# motor_connector_board.net
KiCad netlist of a schematic drawn in EAGLE
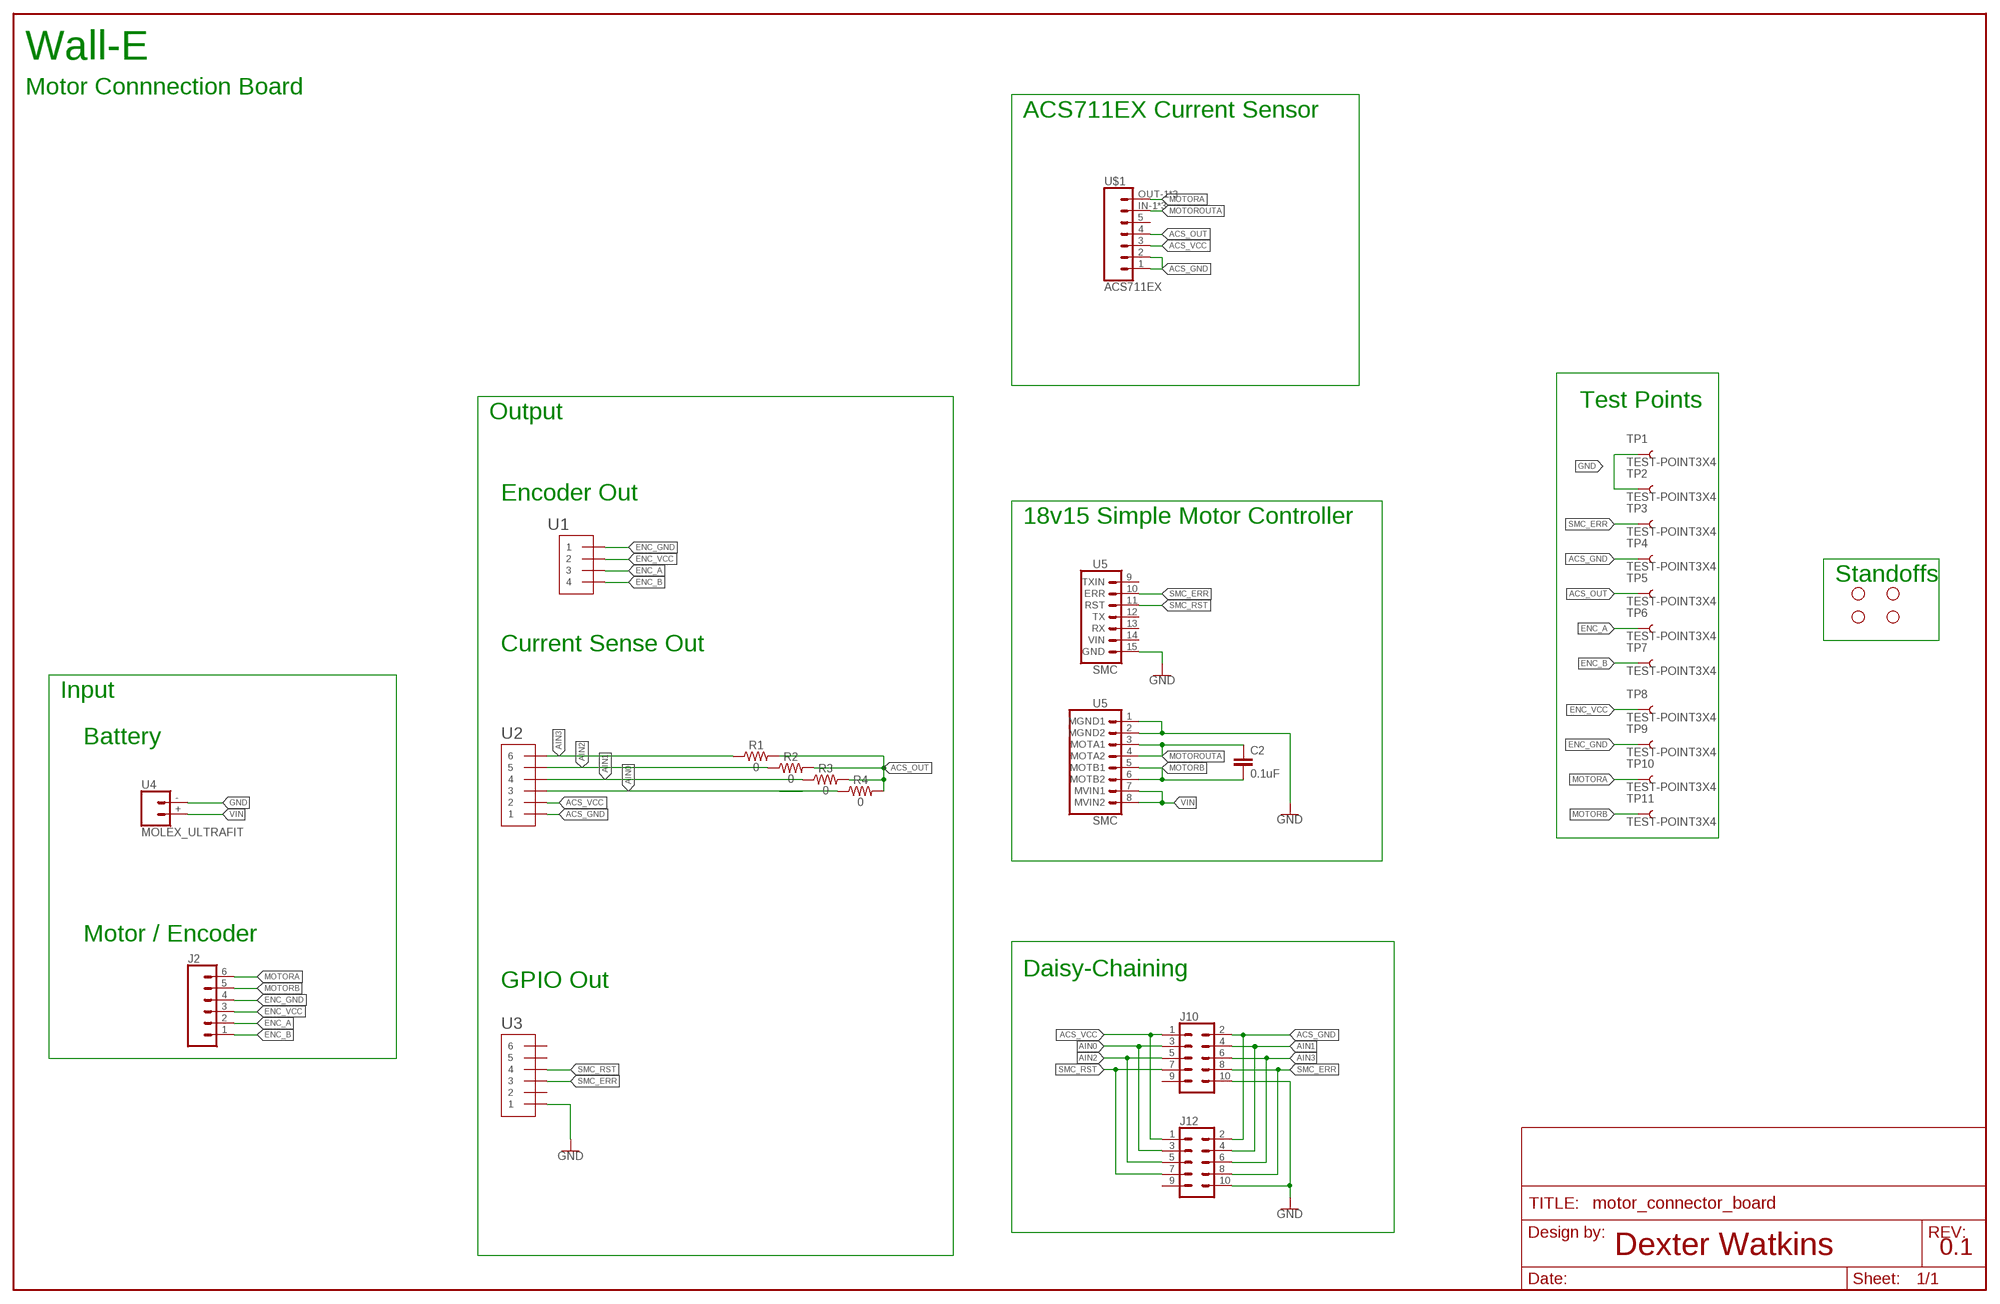
[diagram p0: schematic, sheet 1]

(export (version "E")
  (design (tool "Eeschema 10.0.6"))
  (components
    (comp (ref "C2")
      (value "0.1uF")
      (footprint "eagle-import:0603")
      (libsource (lib "eagle-import") (part "1.0NF/1000PF-0603-50V-10%"))
    )
    (comp (ref "FRAME1")
      (value "FRAME-LEDGER")
      (footprint "eagle-import:CREATIVE_COMMONS")
      (libsource (lib "eagle-import") (part "FRAME-LEDGER"))
    )
    (comp (ref "H1")
      (value "STAND-OFF")
      (footprint "eagle-import:STAND-OFF")
      (libsource (lib "eagle-import") (part "STAND-OFF"))
    )
    (comp (ref "H2")
      (value "STAND-OFF")
      (footprint "eagle-import:STAND-OFF")
      (libsource (lib "eagle-import") (part "STAND-OFF"))
    )
    (comp (ref "H3")
      (value "STAND-OFF")
      (footprint "eagle-import:STAND-OFF")
      (libsource (lib "eagle-import") (part "STAND-OFF"))
    )
    (comp (ref "H4")
      (value "STAND-OFF")
      (footprint "eagle-import:STAND-OFF")
      (libsource (lib "eagle-import") (part "STAND-OFF"))
    )
    (comp (ref "J2")
      (value "CONN_06LONGPADS")
      (footprint "eagle-import:1X06_LONGPADS")
      (libsource (lib "eagle-import") (part "CONN_06LONGPADS"))
    )
    (comp (ref "J10")
      (value "CONN_05X2SHD_LOCK")
      (footprint "eagle-import:2X5-SHROUDED_LOCK")
      (libsource (lib "eagle-import") (part "CONN_05X2SHD_LOCK"))
    )
    (comp (ref "J12")
      (value "CONN_05X2SHD_LOCK")
      (footprint "eagle-import:2X5-SHROUDED_LOCK")
      (libsource (lib "eagle-import") (part "CONN_05X2SHD_LOCK"))
    )
    (comp (ref "R1")
      (value "0")
      (footprint "eagle-import:0603")
      (libsource (lib "eagle-import") (part "0OHM-0603-1/10W-5%"))
    )
    (comp (ref "R2")
      (value "0")
      (footprint "eagle-import:0603")
      (libsource (lib "eagle-import") (part "0OHM-0603-1/10W-5%"))
    )
    (comp (ref "R3")
      (value "0")
      (footprint "eagle-import:0603")
      (libsource (lib "eagle-import") (part "0OHM-0603-1/10W-5%"))
    )
    (comp (ref "R4")
      (value "0")
      (footprint "eagle-import:0603")
      (libsource (lib "eagle-import") (part "0OHM-0603-1/10W-5%"))
    )
    (comp (ref "TP1")
      (value "TEST-POINT3X4")
      (footprint "eagle-import:PAD.03X.04")
      (libsource (lib "eagle-import") (part "TEST-POINT3X4"))
    )
    (comp (ref "TP2")
      (value "TEST-POINT3X4")
      (footprint "eagle-import:PAD.03X.04")
      (libsource (lib "eagle-import") (part "TEST-POINT3X4"))
    )
    (comp (ref "TP3")
      (value "TEST-POINT3X4")
      (footprint "eagle-import:PAD.03X.04")
      (libsource (lib "eagle-import") (part "TEST-POINT3X4"))
    )
    (comp (ref "TP4")
      (value "TEST-POINT3X4")
      (footprint "eagle-import:PAD.03X.04")
      (libsource (lib "eagle-import") (part "TEST-POINT3X4"))
    )
    (comp (ref "TP5")
      (value "TEST-POINT3X4")
      (footprint "eagle-import:PAD.03X.04")
      (libsource (lib "eagle-import") (part "TEST-POINT3X4"))
    )
    (comp (ref "TP6")
      (value "TEST-POINT3X4")
      (footprint "eagle-import:PAD.03X.04")
      (libsource (lib "eagle-import") (part "TEST-POINT3X4"))
    )
    (comp (ref "TP7")
      (value "TEST-POINT3X4")
      (footprint "eagle-import:PAD.03X.04")
      (libsource (lib "eagle-import") (part "TEST-POINT3X4"))
    )
    (comp (ref "TP8")
      (value "TEST-POINT3X4")
      (footprint "eagle-import:PAD.03X.04")
      (libsource (lib "eagle-import") (part "TEST-POINT3X4"))
    )
    (comp (ref "TP9")
      (value "TEST-POINT3X4")
      (footprint "eagle-import:PAD.03X.04")
      (libsource (lib "eagle-import") (part "TEST-POINT3X4"))
    )
    (comp (ref "TP10")
      (value "TEST-POINT3X4")
      (footprint "eagle-import:PAD.03X.04")
      (libsource (lib "eagle-import") (part "TEST-POINT3X4"))
    )
    (comp (ref "TP11")
      (value "TEST-POINT3X4")
      (footprint "eagle-import:PAD.03X.04")
      (libsource (lib "eagle-import") (part "TEST-POINT3X4"))
    )
    (comp (ref "U$1")
      (value "ACS711EX")
      (footprint "eagle-import:ACS_CURRENT_SENSOR")
      (libsource (lib "eagle-import") (part "ACS711EX"))
    )
    (comp (ref "U1")
      (value "JST_SH_4")
      (footprint "eagle-import:JST_SH_4_SMD")
      (libsource (lib "eagle-import") (part "JST_SH_4"))
    )
    (comp (ref "U2")
      (value "JST_SH_6")
      (footprint "eagle-import:JST_SH_6")
      (libsource (lib "eagle-import") (part "JST_SH_6"))
    )
    (comp (ref "U3")
      (value "JST_SH_6")
      (footprint "eagle-import:JST_SH_6")
      (libsource (lib "eagle-import") (part "JST_SH_6"))
    )
    (comp (ref "U4")
      (value "MOLEX_ULTRAFIT")
      (footprint "eagle-import:MOLEX_ULTRAFIT-2CKT")
      (libsource (lib "eagle-import") (part "MOLEX_ULTRAFIT"))
    )
    (comp (ref "U5")
      (value "SMC")
      (footprint "eagle-import:SMC")
      (libsource (lib "eagle-import") (part "SMC"))
    )
  )
  (nets
    (net (code "1") (name "ACS_GND") (class "Default")
      (node (ref "J10") (pin "2") (pinfunction "2_2") (pintype "passive"))
      (node (ref "J12") (pin "2") (pinfunction "2_2") (pintype "passive"))
      (node (ref "TP4") (pin "P$1") (pinfunction "1_P$1") (pintype "bidirectional"))
      (node (ref "U$1") (pin "1") (pinfunction "1_1") (pintype "passive"))
      (node (ref "U$1") (pin "2") (pinfunction "2_2") (pintype "passive"))
      (node (ref "U2") (pin "1") (pinfunction "1_1") (pintype "bidirectional"))
    )
    (net (code "2") (name "ACS_OUT") (class "Default")
      (node (ref "R1") (pin "2") (pinfunction "2_2") (pintype "passive"))
      (node (ref "R2") (pin "2") (pinfunction "2_2") (pintype "passive"))
      (node (ref "R3") (pin "2") (pinfunction "2_2") (pintype "passive"))
      (node (ref "R4") (pin "2") (pinfunction "2_2") (pintype "passive"))
      (node (ref "TP5") (pin "P$1") (pinfunction "1_P$1") (pintype "bidirectional"))
      (node (ref "U$1") (pin "4") (pinfunction "4_4") (pintype "passive"))
    )
    (net (code "3") (name "ACS_VCC") (class "Default")
      (node (ref "J10") (pin "1") (pinfunction "1_1") (pintype "passive"))
      (node (ref "J12") (pin "1") (pinfunction "1_1") (pintype "passive"))
      (node (ref "U$1") (pin "3") (pinfunction "3_3") (pintype "passive"))
      (node (ref "U2") (pin "2") (pinfunction "2_2") (pintype "bidirectional"))
    )
    (net (code "4") (name "AIN0") (class "Default")
      (node (ref "J10") (pin "3") (pinfunction "3_3") (pintype "passive"))
      (node (ref "J12") (pin "3") (pinfunction "3_3") (pintype "passive"))
      (node (ref "R4") (pin "1") (pinfunction "1_1") (pintype "passive"))
      (node (ref "U2") (pin "3") (pinfunction "3_3") (pintype "bidirectional"))
    )
    (net (code "5") (name "AIN1") (class "Default")
      (node (ref "J10") (pin "4") (pinfunction "4_4") (pintype "passive"))
      (node (ref "J12") (pin "4") (pinfunction "4_4") (pintype "passive"))
      (node (ref "R3") (pin "1") (pinfunction "1_1") (pintype "passive"))
      (node (ref "U2") (pin "4") (pinfunction "4_4") (pintype "bidirectional"))
    )
    (net (code "6") (name "AIN2") (class "Default")
      (node (ref "J10") (pin "5") (pinfunction "5_5") (pintype "passive"))
      (node (ref "J12") (pin "5") (pinfunction "5_5") (pintype "passive"))
      (node (ref "R2") (pin "1") (pinfunction "1_1") (pintype "passive"))
      (node (ref "U2") (pin "5") (pinfunction "5_5") (pintype "bidirectional"))
    )
    (net (code "7") (name "AIN3") (class "Default")
      (node (ref "J10") (pin "6") (pinfunction "6_6") (pintype "passive"))
      (node (ref "J12") (pin "6") (pinfunction "6_6") (pintype "passive"))
      (node (ref "R1") (pin "1") (pinfunction "1_1") (pintype "passive"))
      (node (ref "U2") (pin "6") (pinfunction "6_6") (pintype "bidirectional"))
    )
    (net (code "8") (name "ENC_A") (class "Default")
      (node (ref "J2") (pin "2") (pinfunction "2_2") (pintype "passive"))
      (node (ref "TP6") (pin "P$1") (pinfunction "1_P$1") (pintype "bidirectional"))
      (node (ref "U1") (pin "3") (pinfunction "3_3") (pintype "bidirectional"))
    )
    (net (code "9") (name "ENC_B") (class "Default")
      (node (ref "J2") (pin "1") (pinfunction "1_1") (pintype "passive"))
      (node (ref "TP7") (pin "P$1") (pinfunction "1_P$1") (pintype "bidirectional"))
      (node (ref "U1") (pin "4") (pinfunction "4_4") (pintype "bidirectional"))
    )
    (net (code "10") (name "ENC_GND") (class "Default")
      (node (ref "J2") (pin "4") (pinfunction "4_4") (pintype "passive"))
      (node (ref "TP9") (pin "P$1") (pinfunction "1_P$1") (pintype "bidirectional"))
      (node (ref "U1") (pin "1") (pinfunction "1_1") (pintype "bidirectional"))
    )
    (net (code "11") (name "ENC_VCC") (class "Default")
      (node (ref "J2") (pin "3") (pinfunction "3_3") (pintype "passive"))
      (node (ref "TP8") (pin "P$1") (pinfunction "1_P$1") (pintype "bidirectional"))
      (node (ref "U1") (pin "2") (pinfunction "2_2") (pintype "bidirectional"))
    )
    (net (code "12") (name "GND") (class "Default")
      (node (ref "J10") (pin "10") (pinfunction "10_10") (pintype "passive"))
      (node (ref "J12") (pin "10") (pinfunction "10_10") (pintype "passive"))
      (node (ref "TP1") (pin "P$1") (pinfunction "1_P$1") (pintype "bidirectional"))
      (node (ref "TP2") (pin "P$1") (pinfunction "1_P$1") (pintype "bidirectional"))
      (node (ref "U3") (pin "1") (pinfunction "1_1") (pintype "bidirectional"))
      (node (ref "U4") (pin "-") (pinfunction "2_-") (pintype "passive"))
      (node (ref "U5") (pin "1") (pinfunction "MGND1_1") (pintype "passive"))
      (node (ref "U5") (pin "15") (pinfunction "GND_15") (pintype "passive"))
      (node (ref "U5") (pin "2") (pinfunction "MGND2_2") (pintype "passive"))
    )
    (net (code "13") (name "MOTORA") (class "Default")
      (node (ref "J2") (pin "6") (pinfunction "6_6") (pintype "passive"))
      (node (ref "TP10") (pin "P$1") (pinfunction "1_P$1") (pintype "bidirectional"))
      (node (ref "U$1") (pin "OUT-1") (pinfunction "7_OUT-1") (pintype "passive"))
      (node (ref "U$1") (pin "OUT-2") (pinfunction "7_OUT-2") (pintype "passive"))
      (node (ref "U$1") (pin "OUT-3") (pinfunction "7_OUT-3") (pintype "passive"))
    )
    (net (code "14") (name "MOTORB") (class "Default")
      (node (ref "C2") (pin "2") (pinfunction "2_2") (pintype "passive"))
      (node (ref "J2") (pin "5") (pinfunction "5_5") (pintype "passive"))
      (node (ref "TP11") (pin "P$1") (pinfunction "1_P$1") (pintype "bidirectional"))
      (node (ref "U5") (pin "5") (pinfunction "MOTB1_5") (pintype "passive"))
      (node (ref "U5") (pin "6") (pinfunction "MOTB2_6") (pintype "passive"))
    )
    (net (code "15") (name "MOTOROUTA") (class "Default")
      (node (ref "C2") (pin "1") (pinfunction "1_1") (pintype "passive"))
      (node (ref "U$1") (pin "IN-1") (pinfunction "6_IN-1") (pintype "passive"))
      (node (ref "U$1") (pin "IN-2") (pinfunction "6_IN-2") (pintype "passive"))
      (node (ref "U$1") (pin "IN-3") (pinfunction "6_IN-3") (pintype "passive"))
      (node (ref "U5") (pin "3") (pinfunction "MOTA1_3") (pintype "passive"))
      (node (ref "U5") (pin "4") (pinfunction "MOTA2_4") (pintype "passive"))
    )
    (net (code "16") (name "SMC_ERR") (class "Default")
      (node (ref "J10") (pin "8") (pinfunction "8_8") (pintype "passive"))
      (node (ref "J12") (pin "8") (pinfunction "8_8") (pintype "passive"))
      (node (ref "TP3") (pin "P$1") (pinfunction "1_P$1") (pintype "bidirectional"))
      (node (ref "U3") (pin "3") (pinfunction "3_3") (pintype "bidirectional"))
      (node (ref "U5") (pin "10") (pinfunction "ERR_10") (pintype "passive"))
    )
    (net (code "17") (name "SMC_RST") (class "Default")
      (node (ref "J10") (pin "7") (pinfunction "7_7") (pintype "passive"))
      (node (ref "J12") (pin "7") (pinfunction "7_7") (pintype "passive"))
      (node (ref "U3") (pin "4") (pinfunction "4_4") (pintype "bidirectional"))
      (node (ref "U5") (pin "11") (pinfunction "RST_11") (pintype "passive"))
    )
    (net (code "18") (name "VIN") (class "Default")
      (node (ref "U4") (pin "+") (pinfunction "1_+") (pintype "passive"))
      (node (ref "U5") (pin "7") (pinfunction "MVIN1_7") (pintype "passive"))
      (node (ref "U5") (pin "8") (pinfunction "MVIN2_8") (pintype "passive"))
    )
    (net (code "19") (name "unconnected-(J10-Pad9)") (class "Default")
      (node (ref "J10") (pin "9") (pinfunction "9_9") (pintype "passive"))
    )
    (net (code "20") (name "unconnected-(J12-Pad9)") (class "Default")
      (node (ref "J12") (pin "9") (pinfunction "9_9") (pintype "passive"))
    )
    (net (code "21") (name "unconnected-(U$1-Pad5)") (class "Default")
      (node (ref "U$1") (pin "5") (pinfunction "5_5") (pintype "passive"))
    )
    (net (code "22") (name "unconnected-(U3-Pad2)") (class "Default")
      (node (ref "U3") (pin "2") (pinfunction "2_2") (pintype "bidirectional"))
    )
    (net (code "23") (name "unconnected-(U3-Pad5)") (class "Default")
      (node (ref "U3") (pin "5") (pinfunction "5_5") (pintype "bidirectional"))
    )
    (net (code "24") (name "unconnected-(U3-Pad6)") (class "Default")
      (node (ref "U3") (pin "6") (pinfunction "6_6") (pintype "bidirectional"))
    )
    (net (code "25") (name "unconnected-(U5-RX-Pad13)") (class "Default")
      (node (ref "U5") (pin "13") (pinfunction "RX_13") (pintype "passive"))
    )
    (net (code "26") (name "unconnected-(U5-TX-Pad12)") (class "Default")
      (node (ref "U5") (pin "12") (pinfunction "TX_12") (pintype "passive"))
    )
    (net (code "27") (name "unconnected-(U5-TXIN-Pad9)") (class "Default")
      (node (ref "U5") (pin "9") (pinfunction "TXIN_9") (pintype "passive"))
    )
    (net (code "28") (name "unconnected-(U5-VIN-Pad14)") (class "Default")
      (node (ref "U5") (pin "14") (pinfunction "VIN_14") (pintype "passive"))
    )
  )
)
